# M606B.net
KiCad netlist of a schematic drawn in EAGLE
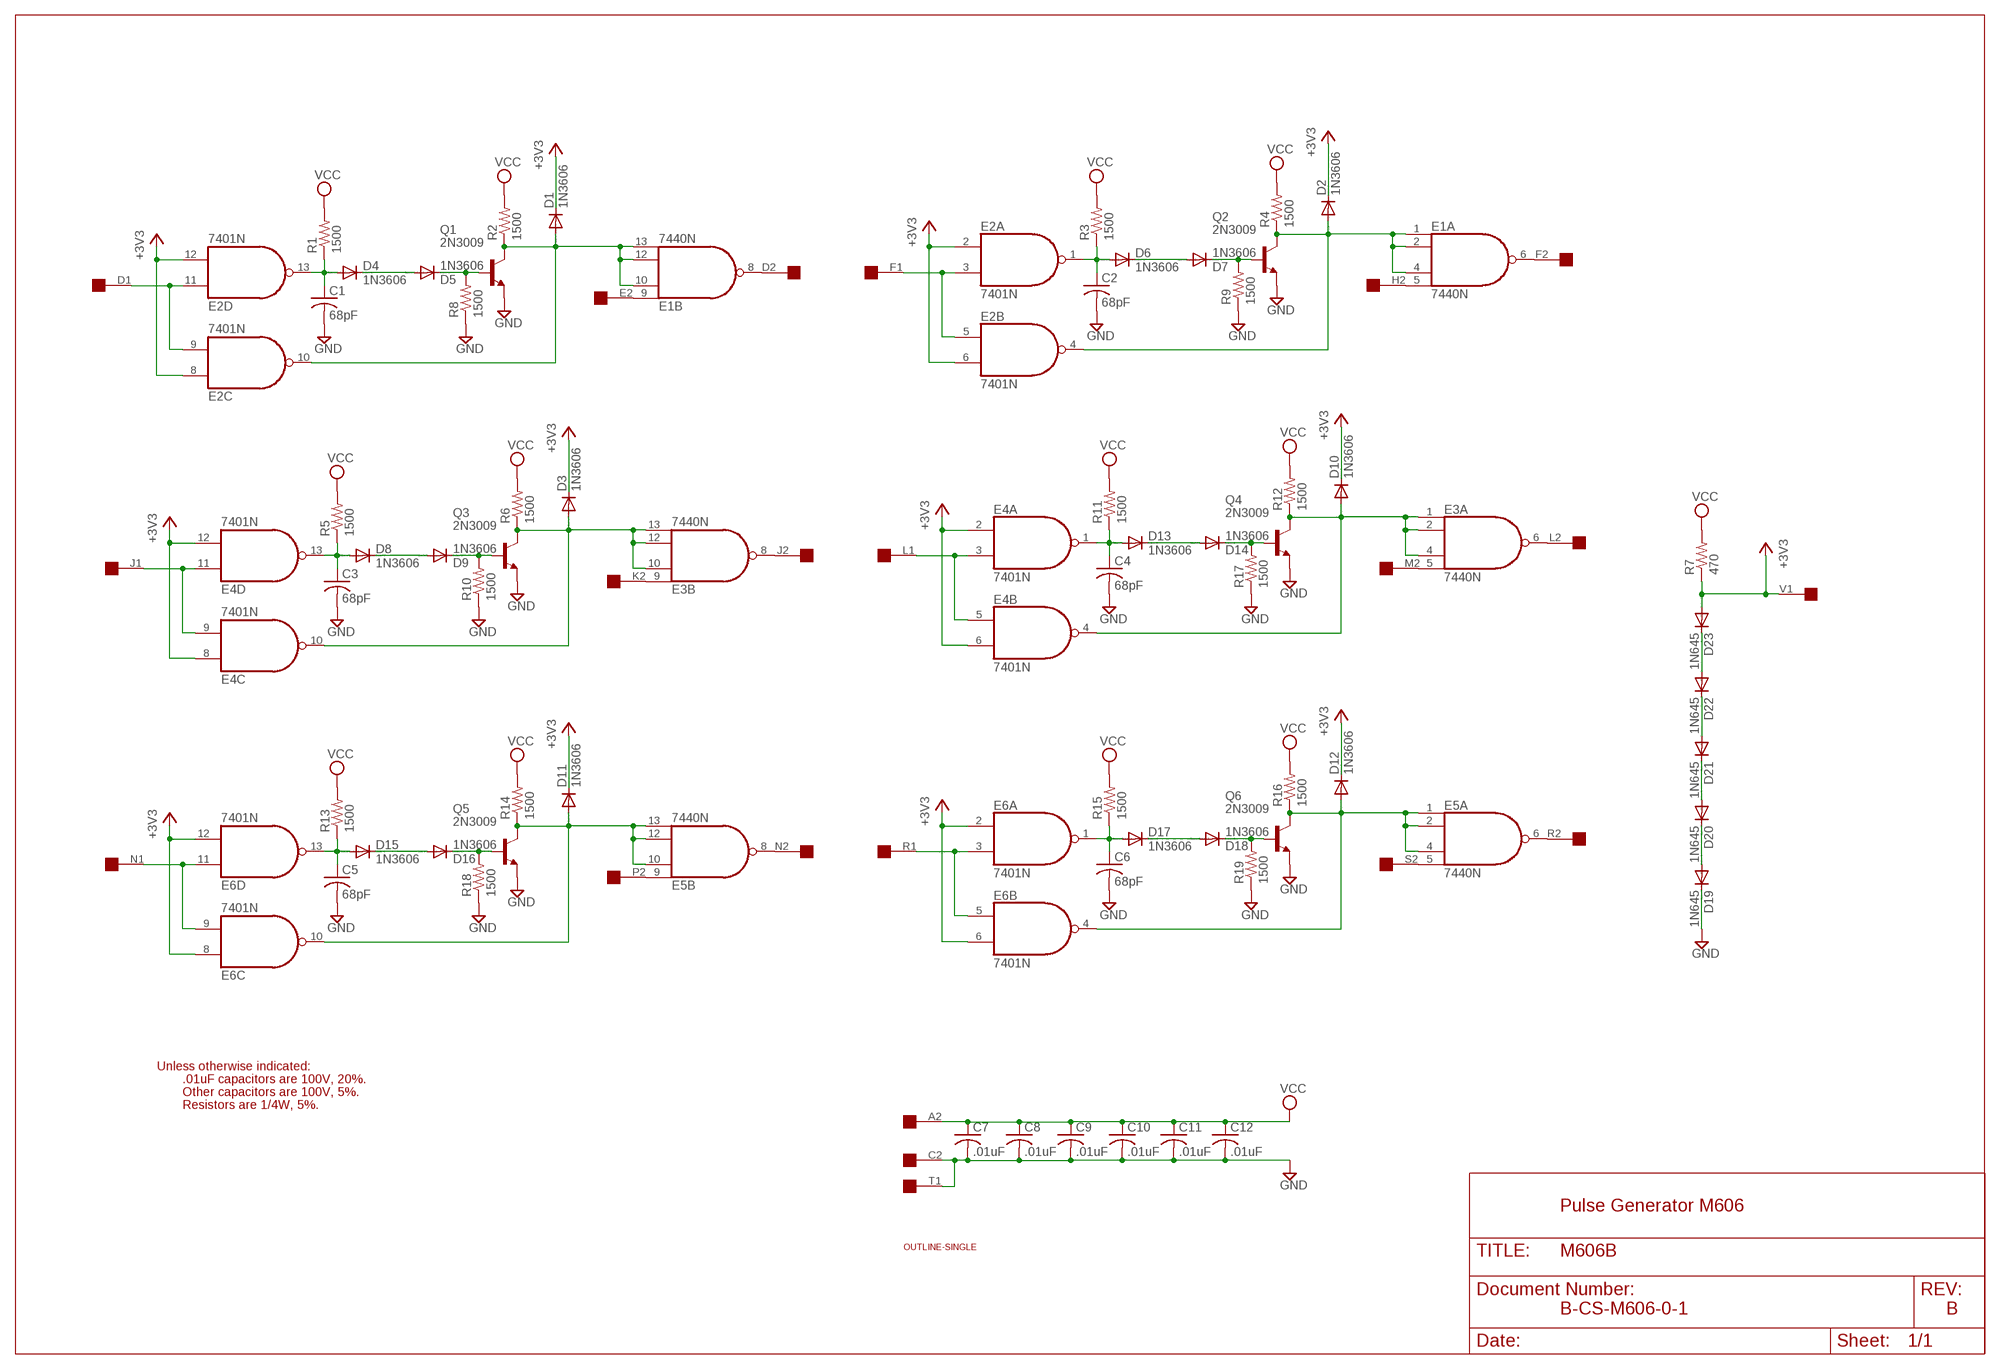
[diagram p0: schematic, sheet 1]

(export (version "E")
  (design (tool "Eeschema 10.0.6"))
  (components
    (comp (ref "C1")
      (value "68pF")
      (footprint "eagle-import:C075-032X103")
      (libsource (lib "eagle-import") (part "C-US075-032X103"))
    )
    (comp (ref "C2")
      (value "68pF")
      (footprint "eagle-import:C075-032X103")
      (libsource (lib "eagle-import") (part "C-US075-032X103"))
    )
    (comp (ref "C3")
      (value "68pF")
      (footprint "eagle-import:C075-032X103")
      (libsource (lib "eagle-import") (part "C-US075-032X103"))
    )
    (comp (ref "C4")
      (value "68pF")
      (footprint "eagle-import:C075-032X103")
      (libsource (lib "eagle-import") (part "C-US075-032X103"))
    )
    (comp (ref "C5")
      (value "68pF")
      (footprint "eagle-import:C075-032X103")
      (libsource (lib "eagle-import") (part "C-US075-032X103"))
    )
    (comp (ref "C6")
      (value "68pF")
      (footprint "eagle-import:C075-032X103")
      (libsource (lib "eagle-import") (part "C-US075-032X103"))
    )
    (comp (ref "C7")
      (value ".01uF")
      (footprint "eagle-import:C050-025X075")
      (libsource (lib "eagle-import") (part "C-US050-025X075"))
    )
    (comp (ref "C8")
      (value ".01uF")
      (footprint "eagle-import:C050-025X075")
      (libsource (lib "eagle-import") (part "C-US050-025X075"))
    )
    (comp (ref "C9")
      (value ".01uF")
      (footprint "eagle-import:C050-025X075")
      (libsource (lib "eagle-import") (part "C-US050-025X075"))
    )
    (comp (ref "C10")
      (value ".01uF")
      (footprint "eagle-import:C050-025X075")
      (libsource (lib "eagle-import") (part "C-US050-025X075"))
    )
    (comp (ref "C11")
      (value ".01uF")
      (footprint "eagle-import:C050-025X075")
      (libsource (lib "eagle-import") (part "C-US050-025X075"))
    )
    (comp (ref "C12")
      (value ".01uF")
      (footprint "eagle-import:C050-025X075")
      (libsource (lib "eagle-import") (part "C-US050-025X075"))
    )
    (comp (ref "D1")
      (value "1N3606")
      (footprint "eagle-import:DO35-10")
      (libsource (lib "eagle-import") (part "1N4148DO35-10"))
    )
    (comp (ref "D2")
      (value "1N3606")
      (footprint "eagle-import:DO35-10")
      (libsource (lib "eagle-import") (part "1N4148DO35-10"))
    )
    (comp (ref "D3")
      (value "1N3606")
      (footprint "eagle-import:DO35-10")
      (libsource (lib "eagle-import") (part "1N4148DO35-10"))
    )
    (comp (ref "D4")
      (value "1N3606")
      (footprint "eagle-import:DO35-10")
      (libsource (lib "eagle-import") (part "1N4148DO35-10"))
    )
    (comp (ref "D5")
      (value "1N3606")
      (footprint "eagle-import:DO35-10")
      (libsource (lib "eagle-import") (part "1N4148DO35-10"))
    )
    (comp (ref "D6")
      (value "1N3606")
      (footprint "eagle-import:DO35-10")
      (libsource (lib "eagle-import") (part "1N4148DO35-10"))
    )
    (comp (ref "D7")
      (value "1N3606")
      (footprint "eagle-import:DO35-10")
      (libsource (lib "eagle-import") (part "1N4148DO35-10"))
    )
    (comp (ref "D8")
      (value "1N3606")
      (footprint "eagle-import:DO35-10")
      (libsource (lib "eagle-import") (part "1N4148DO35-10"))
    )
    (comp (ref "D9")
      (value "1N3606")
      (footprint "eagle-import:DO35-10")
      (libsource (lib "eagle-import") (part "1N4148DO35-10"))
    )
    (comp (ref "D10")
      (value "1N3606")
      (footprint "eagle-import:DO35-10")
      (libsource (lib "eagle-import") (part "1N4148DO35-10"))
    )
    (comp (ref "D11")
      (value "1N3606")
      (footprint "eagle-import:DO35-10")
      (libsource (lib "eagle-import") (part "1N4148DO35-10"))
    )
    (comp (ref "D12")
      (value "1N3606")
      (footprint "eagle-import:DO35-10")
      (libsource (lib "eagle-import") (part "1N4148DO35-10"))
    )
    (comp (ref "D13")
      (value "1N3606")
      (footprint "eagle-import:DO35-10")
      (libsource (lib "eagle-import") (part "1N4148DO35-10"))
    )
    (comp (ref "D14")
      (value "1N3606")
      (footprint "eagle-import:DO35-10")
      (libsource (lib "eagle-import") (part "1N4148DO35-10"))
    )
    (comp (ref "D15")
      (value "1N3606")
      (footprint "eagle-import:DO35-10")
      (libsource (lib "eagle-import") (part "1N4148DO35-10"))
    )
    (comp (ref "D16")
      (value "1N3606")
      (footprint "eagle-import:DO35-10")
      (libsource (lib "eagle-import") (part "1N4148DO35-10"))
    )
    (comp (ref "D17")
      (value "1N3606")
      (footprint "eagle-import:DO35-10")
      (libsource (lib "eagle-import") (part "1N4148DO35-10"))
    )
    (comp (ref "D18")
      (value "1N3606")
      (footprint "eagle-import:DO35-10")
      (libsource (lib "eagle-import") (part "1N4148DO35-10"))
    )
    (comp (ref "D19")
      (value "1N645")
      (footprint "eagle-import:DO35-10")
      (libsource (lib "eagle-import") (part "1N4148DO35-10"))
    )
    (comp (ref "D20")
      (value "1N645")
      (footprint "eagle-import:DO35-10")
      (libsource (lib "eagle-import") (part "1N4148DO35-10"))
    )
    (comp (ref "D21")
      (value "1N645")
      (footprint "eagle-import:DO35-10")
      (libsource (lib "eagle-import") (part "1N4148DO35-10"))
    )
    (comp (ref "D22")
      (value "1N645")
      (footprint "eagle-import:DO35-10")
      (libsource (lib "eagle-import") (part "1N4148DO35-10"))
    )
    (comp (ref "D23")
      (value "1N645")
      (footprint "eagle-import:DO35-10")
      (libsource (lib "eagle-import") (part "1N4148DO35-10"))
    )
    (comp (ref "E1")
      (value "7440N")
      (footprint "eagle-import:DIL14")
      (libsource (lib "eagle-import") (part "7420NS"))
    )
    (comp (ref "E2")
      (value "7401N")
      (footprint "eagle-import:DIL14")
      (libsource (lib "eagle-import") (part "7401NLS"))
    )
    (comp (ref "E3")
      (value "7440N")
      (footprint "eagle-import:DIL14")
      (libsource (lib "eagle-import") (part "7420NS"))
    )
    (comp (ref "E4")
      (value "7401N")
      (footprint "eagle-import:DIL14")
      (libsource (lib "eagle-import") (part "7401NLS"))
    )
    (comp (ref "E5")
      (value "7440N")
      (footprint "eagle-import:DIL14")
      (libsource (lib "eagle-import") (part "7420NS"))
    )
    (comp (ref "E6")
      (value "7401N")
      (footprint "eagle-import:DIL14")
      (libsource (lib "eagle-import") (part "7401NLS"))
    )
    (comp (ref "Q1")
      (value "2N3009")
      (footprint "eagle-import:TO39")
      (libsource (lib "eagle-import") (part "2N3019"))
    )
    (comp (ref "Q2")
      (value "2N3009")
      (footprint "eagle-import:TO39")
      (libsource (lib "eagle-import") (part "2N3019"))
    )
    (comp (ref "Q3")
      (value "2N3009")
      (footprint "eagle-import:TO39")
      (libsource (lib "eagle-import") (part "2N3019"))
    )
    (comp (ref "Q4")
      (value "2N3009")
      (footprint "eagle-import:TO39")
      (libsource (lib "eagle-import") (part "2N3019"))
    )
    (comp (ref "Q5")
      (value "2N3009")
      (footprint "eagle-import:TO39")
      (libsource (lib "eagle-import") (part "2N3019"))
    )
    (comp (ref "Q6")
      (value "2N3009")
      (footprint "eagle-import:TO39")
      (libsource (lib "eagle-import") (part "2N3019"))
    )
    (comp (ref "R1")
      (value "1500")
      (footprint "eagle-import:0207_10")
      (libsource (lib "eagle-import") (part "R-US_0207/10"))
    )
    (comp (ref "R2")
      (value "1500")
      (footprint "eagle-import:0207_10")
      (libsource (lib "eagle-import") (part "R-US_0207/10"))
    )
    (comp (ref "R3")
      (value "1500")
      (footprint "eagle-import:0207_10")
      (libsource (lib "eagle-import") (part "R-US_0207/10"))
    )
    (comp (ref "R4")
      (value "1500")
      (footprint "eagle-import:0207_10")
      (libsource (lib "eagle-import") (part "R-US_0207/10"))
    )
    (comp (ref "R5")
      (value "1500")
      (footprint "eagle-import:0207_10")
      (libsource (lib "eagle-import") (part "R-US_0207/10"))
    )
    (comp (ref "R6")
      (value "1500")
      (footprint "eagle-import:0207_10")
      (libsource (lib "eagle-import") (part "R-US_0207/10"))
    )
    (comp (ref "R7")
      (value "470")
      (footprint "eagle-import:0207_10")
      (libsource (lib "eagle-import") (part "R-US_0207/10"))
    )
    (comp (ref "R8")
      (value "1500")
      (footprint "eagle-import:0207_10")
      (libsource (lib "eagle-import") (part "R-US_0207/10"))
    )
    (comp (ref "R9")
      (value "1500")
      (footprint "eagle-import:0207_10")
      (libsource (lib "eagle-import") (part "R-US_0207/10"))
    )
    (comp (ref "R10")
      (value "1500")
      (footprint "eagle-import:0207_10")
      (libsource (lib "eagle-import") (part "R-US_0207/10"))
    )
    (comp (ref "R11")
      (value "1500")
      (footprint "eagle-import:0207_10")
      (libsource (lib "eagle-import") (part "R-US_0207/10"))
    )
    (comp (ref "R12")
      (value "1500")
      (footprint "eagle-import:0207_10")
      (libsource (lib "eagle-import") (part "R-US_0207/10"))
    )
    (comp (ref "R13")
      (value "1500")
      (footprint "eagle-import:0207_10")
      (libsource (lib "eagle-import") (part "R-US_0207/10"))
    )
    (comp (ref "R14")
      (value "1500")
      (footprint "eagle-import:0207_10")
      (libsource (lib "eagle-import") (part "R-US_0207/10"))
    )
    (comp (ref "R15")
      (value "1500")
      (footprint "eagle-import:0207_10")
      (libsource (lib "eagle-import") (part "R-US_0207/10"))
    )
    (comp (ref "R16")
      (value "1500")
      (footprint "eagle-import:0207_10")
      (libsource (lib "eagle-import") (part "R-US_0207/10"))
    )
    (comp (ref "R17")
      (value "1500")
      (footprint "eagle-import:0207_10")
      (libsource (lib "eagle-import") (part "R-US_0207/10"))
    )
    (comp (ref "R18")
      (value "1500")
      (footprint "eagle-import:0207_10")
      (libsource (lib "eagle-import") (part "R-US_0207/10"))
    )
    (comp (ref "R19")
      (value "1500")
      (footprint "eagle-import:0207_10")
      (libsource (lib "eagle-import") (part "R-US_0207/10"))
    )
    (comp (ref "U$2")
      (value "SINGLE")
      (footprint "eagle-import:EDGE-CON2")
      (libsource (lib "eagle-import") (part "SINGLE"))
    )
    (comp (ref "U$4")
      (value "OUTLINE-SINGLE")
      (footprint "eagle-import:SINGLE")
      (libsource (lib "eagle-import") (part "OUTLINE-SINGLE"))
    )
  )
  (nets
    (net (code "1") (name "+3V3") (class "Default")
      (node (ref "D1") (pin "C") (pinfunction "C_C") (pintype "passive"))
      (node (ref "D10") (pin "C") (pinfunction "C_C") (pintype "passive"))
      (node (ref "D11") (pin "C") (pinfunction "C_C") (pintype "passive"))
      (node (ref "D12") (pin "C") (pinfunction "C_C") (pintype "passive"))
      (node (ref "D2") (pin "C") (pinfunction "C_C") (pintype "passive"))
      (node (ref "D23") (pin "A") (pinfunction "A_A") (pintype "passive"))
      (node (ref "D3") (pin "C") (pinfunction "C_C") (pintype "passive"))
      (node (ref "E2") (pin "12") (pinfunction "I1_12") (pintype "input"))
      (node (ref "E2") (pin "2") (pinfunction "I0_2") (pintype "input"))
      (node (ref "E2") (pin "6") (pinfunction "I1_6") (pintype "input"))
      (node (ref "E2") (pin "8") (pinfunction "I0_8") (pintype "input"))
      (node (ref "E4") (pin "12") (pinfunction "I1_12") (pintype "input"))
      (node (ref "E4") (pin "2") (pinfunction "I0_2") (pintype "input"))
      (node (ref "E4") (pin "6") (pinfunction "I1_6") (pintype "input"))
      (node (ref "E4") (pin "8") (pinfunction "I0_8") (pintype "input"))
      (node (ref "E6") (pin "12") (pinfunction "I1_12") (pintype "input"))
      (node (ref "E6") (pin "2") (pinfunction "I0_2") (pintype "input"))
      (node (ref "E6") (pin "6") (pinfunction "I1_6") (pintype "input"))
      (node (ref "E6") (pin "8") (pinfunction "I0_8") (pintype "input"))
      (node (ref "R7") (pin "1") (pinfunction "1_1") (pintype "passive"))
      (node (ref "U$2") (pin "V1") (pinfunction "1_V1") (pintype "bidirectional"))
    )
    (net (code "2") (name "GND") (class "Default")
      (node (ref "C1") (pin "2") (pinfunction "2_2") (pintype "passive"))
      (node (ref "C10") (pin "2") (pinfunction "2_2") (pintype "passive"))
      (node (ref "C11") (pin "2") (pinfunction "2_2") (pintype "passive"))
      (node (ref "C12") (pin "2") (pinfunction "2_2") (pintype "passive"))
      (node (ref "C2") (pin "2") (pinfunction "2_2") (pintype "passive"))
      (node (ref "C3") (pin "2") (pinfunction "2_2") (pintype "passive"))
      (node (ref "C4") (pin "2") (pinfunction "2_2") (pintype "passive"))
      (node (ref "C5") (pin "2") (pinfunction "2_2") (pintype "passive"))
      (node (ref "C6") (pin "2") (pinfunction "2_2") (pintype "passive"))
      (node (ref "C7") (pin "2") (pinfunction "2_2") (pintype "passive"))
      (node (ref "C8") (pin "2") (pinfunction "2_2") (pintype "passive"))
      (node (ref "C9") (pin "2") (pinfunction "2_2") (pintype "passive"))
      (node (ref "D19") (pin "C") (pinfunction "C_C") (pintype "passive"))
      (node (ref "Q1") (pin "1") (pinfunction "E_1") (pintype "passive"))
      (node (ref "Q2") (pin "1") (pinfunction "E_1") (pintype "passive"))
      (node (ref "Q3") (pin "1") (pinfunction "E_1") (pintype "passive"))
      (node (ref "Q4") (pin "1") (pinfunction "E_1") (pintype "passive"))
      (node (ref "Q5") (pin "1") (pinfunction "E_1") (pintype "passive"))
      (node (ref "Q6") (pin "1") (pinfunction "E_1") (pintype "passive"))
      (node (ref "R10") (pin "1") (pinfunction "1_1") (pintype "passive"))
      (node (ref "R17") (pin "1") (pinfunction "1_1") (pintype "passive"))
      (node (ref "R18") (pin "1") (pinfunction "1_1") (pintype "passive"))
      (node (ref "R19") (pin "1") (pinfunction "1_1") (pintype "passive"))
      (node (ref "R8") (pin "1") (pinfunction "1_1") (pintype "passive"))
      (node (ref "R9") (pin "1") (pinfunction "1_1") (pintype "passive"))
      (node (ref "U$2") (pin "C2") (pinfunction "1_C2") (pintype "bidirectional"))
      (node (ref "U$2") (pin "T1") (pinfunction "1_T1") (pintype "bidirectional"))
    )
    (net (code "3") (name "Net-(D4-PadC)") (class "Default")
      (node (ref "D4") (pin "C") (pinfunction "C_C") (pintype "passive"))
      (node (ref "D5") (pin "A") (pinfunction "A_A") (pintype "passive"))
    )
    (net (code "4") (name "Net-(D6-PadC)") (class "Default")
      (node (ref "D6") (pin "C") (pinfunction "C_C") (pintype "passive"))
      (node (ref "D7") (pin "A") (pinfunction "A_A") (pintype "passive"))
    )
    (net (code "5") (name "Net-(D8-PadC)") (class "Default")
      (node (ref "D8") (pin "C") (pinfunction "C_C") (pintype "passive"))
      (node (ref "D9") (pin "A") (pinfunction "A_A") (pintype "passive"))
    )
    (net (code "6") (name "Net-(D13-PadC)") (class "Default")
      (node (ref "D13") (pin "C") (pinfunction "C_C") (pintype "passive"))
      (node (ref "D14") (pin "A") (pinfunction "A_A") (pintype "passive"))
    )
    (net (code "7") (name "Net-(D15-PadC)") (class "Default")
      (node (ref "D15") (pin "C") (pinfunction "C_C") (pintype "passive"))
      (node (ref "D16") (pin "A") (pinfunction "A_A") (pintype "passive"))
    )
    (net (code "8") (name "Net-(D17-PadC)") (class "Default")
      (node (ref "D17") (pin "C") (pinfunction "C_C") (pintype "passive"))
      (node (ref "D18") (pin "A") (pinfunction "A_A") (pintype "passive"))
    )
    (net (code "9") (name "Net-(D19-PadA)") (class "Default")
      (node (ref "D19") (pin "A") (pinfunction "A_A") (pintype "passive"))
      (node (ref "D20") (pin "C") (pinfunction "C_C") (pintype "passive"))
    )
    (net (code "10") (name "Net-(D20-PadA)") (class "Default")
      (node (ref "D20") (pin "A") (pinfunction "A_A") (pintype "passive"))
      (node (ref "D21") (pin "C") (pinfunction "C_C") (pintype "passive"))
    )
    (net (code "11") (name "Net-(D21-PadA)") (class "Default")
      (node (ref "D21") (pin "A") (pinfunction "A_A") (pintype "passive"))
      (node (ref "D22") (pin "C") (pinfunction "C_C") (pintype "passive"))
    )
    (net (code "12") (name "Net-(D22-PadA)") (class "Default")
      (node (ref "D22") (pin "A") (pinfunction "A_A") (pintype "passive"))
      (node (ref "D23") (pin "C") (pinfunction "C_C") (pintype "passive"))
    )
    (net (code "13") (name "Net-(E1A-I0)") (class "Default")
      (node (ref "D2") (pin "A") (pinfunction "A_A") (pintype "passive"))
      (node (ref "E1") (pin "1") (pinfunction "I0_1") (pintype "input"))
      (node (ref "E1") (pin "2") (pinfunction "I1_2") (pintype "input"))
      (node (ref "E1") (pin "4") (pinfunction "I2_4") (pintype "input"))
      (node (ref "E2") (pin "4") (pinfunction "O_4") (pintype "open_collector"))
      (node (ref "Q2") (pin "3") (pinfunction "C_3") (pintype "passive"))
      (node (ref "R4") (pin "1") (pinfunction "1_1") (pintype "passive"))
    )
    (net (code "14") (name "Net-(E1A-I3)") (class "Default")
      (node (ref "E1") (pin "5") (pinfunction "I3_5") (pintype "input"))
      (node (ref "U$2") (pin "H2") (pinfunction "1_H2") (pintype "bidirectional"))
    )
    (net (code "15") (name "Net-(E1A-O)") (class "Default")
      (node (ref "E1") (pin "6") (pinfunction "O_6") (pintype "output"))
      (node (ref "U$2") (pin "F2") (pinfunction "1_F2") (pintype "bidirectional"))
    )
    (net (code "16") (name "Net-(E1B-I0)") (class "Default")
      (node (ref "E1") (pin "9") (pinfunction "I0_9") (pintype "input"))
      (node (ref "U$2") (pin "E2") (pinfunction "1_E2") (pintype "bidirectional"))
    )
    (net (code "17") (name "Net-(E1B-I1)") (class "Default")
      (node (ref "D1") (pin "A") (pinfunction "A_A") (pintype "passive"))
      (node (ref "E1") (pin "10") (pinfunction "I1_10") (pintype "input"))
      (node (ref "E1") (pin "12") (pinfunction "I2_12") (pintype "input"))
      (node (ref "E1") (pin "13") (pinfunction "I3_13") (pintype "input"))
      (node (ref "E2") (pin "10") (pinfunction "O_10") (pintype "open_collector"))
      (node (ref "Q1") (pin "3") (pinfunction "C_3") (pintype "passive"))
      (node (ref "R2") (pin "1") (pinfunction "1_1") (pintype "passive"))
    )
    (net (code "18") (name "Net-(E1B-O)") (class "Default")
      (node (ref "E1") (pin "8") (pinfunction "O_8") (pintype "output"))
      (node (ref "U$2") (pin "D2") (pinfunction "1_D2") (pintype "bidirectional"))
    )
    (net (code "19") (name "Net-(E2A-I1)") (class "Default")
      (node (ref "E2") (pin "3") (pinfunction "I1_3") (pintype "input"))
      (node (ref "E2") (pin "5") (pinfunction "I0_5") (pintype "input"))
      (node (ref "U$2") (pin "F1") (pinfunction "1_F1") (pintype "bidirectional"))
    )
    (net (code "20") (name "Net-(E2A-O)") (class "Default")
      (node (ref "C2") (pin "1") (pinfunction "1_1") (pintype "passive"))
      (node (ref "D6") (pin "A") (pinfunction "A_A") (pintype "passive"))
      (node (ref "E2") (pin "1") (pinfunction "O_1") (pintype "open_collector"))
      (node (ref "R3") (pin "1") (pinfunction "1_1") (pintype "passive"))
    )
    (net (code "21") (name "Net-(E2C-I1)") (class "Default")
      (node (ref "E2") (pin "11") (pinfunction "I0_11") (pintype "input"))
      (node (ref "E2") (pin "9") (pinfunction "I1_9") (pintype "input"))
      (node (ref "U$2") (pin "D1") (pinfunction "1_D1") (pintype "bidirectional"))
    )
    (net (code "22") (name "Net-(E2D-O)") (class "Default")
      (node (ref "C1") (pin "1") (pinfunction "1_1") (pintype "passive"))
      (node (ref "D4") (pin "A") (pinfunction "A_A") (pintype "passive"))
      (node (ref "E2") (pin "13") (pinfunction "O_13") (pintype "open_collector"))
      (node (ref "R1") (pin "1") (pinfunction "1_1") (pintype "passive"))
    )
    (net (code "23") (name "Net-(E3A-I0)") (class "Default")
      (node (ref "D10") (pin "A") (pinfunction "A_A") (pintype "passive"))
      (node (ref "E3") (pin "1") (pinfunction "I0_1") (pintype "input"))
      (node (ref "E3") (pin "2") (pinfunction "I1_2") (pintype "input"))
      (node (ref "E3") (pin "4") (pinfunction "I2_4") (pintype "input"))
      (node (ref "E4") (pin "4") (pinfunction "O_4") (pintype "open_collector"))
      (node (ref "Q4") (pin "3") (pinfunction "C_3") (pintype "passive"))
      (node (ref "R12") (pin "1") (pinfunction "1_1") (pintype "passive"))
    )
    (net (code "24") (name "Net-(E3A-I3)") (class "Default")
      (node (ref "E3") (pin "5") (pinfunction "I3_5") (pintype "input"))
      (node (ref "U$2") (pin "M2") (pinfunction "1_M2") (pintype "bidirectional"))
    )
    (net (code "25") (name "Net-(E3A-O)") (class "Default")
      (node (ref "E3") (pin "6") (pinfunction "O_6") (pintype "output"))
      (node (ref "U$2") (pin "L2") (pinfunction "1_L2") (pintype "bidirectional"))
    )
    (net (code "26") (name "Net-(E3B-I0)") (class "Default")
      (node (ref "E3") (pin "9") (pinfunction "I0_9") (pintype "input"))
      (node (ref "U$2") (pin "K2") (pinfunction "1_K2") (pintype "bidirectional"))
    )
    (net (code "27") (name "Net-(E3B-I1)") (class "Default")
      (node (ref "D3") (pin "A") (pinfunction "A_A") (pintype "passive"))
      (node (ref "E3") (pin "10") (pinfunction "I1_10") (pintype "input"))
      (node (ref "E3") (pin "12") (pinfunction "I2_12") (pintype "input"))
      (node (ref "E3") (pin "13") (pinfunction "I3_13") (pintype "input"))
      (node (ref "E4") (pin "10") (pinfunction "O_10") (pintype "open_collector"))
      (node (ref "Q3") (pin "3") (pinfunction "C_3") (pintype "passive"))
      (node (ref "R6") (pin "1") (pinfunction "1_1") (pintype "passive"))
    )
    (net (code "28") (name "Net-(E3B-O)") (class "Default")
      (node (ref "E3") (pin "8") (pinfunction "O_8") (pintype "output"))
      (node (ref "U$2") (pin "J2") (pinfunction "1_J2") (pintype "bidirectional"))
    )
    (net (code "29") (name "Net-(E4A-I1)") (class "Default")
      (node (ref "E4") (pin "3") (pinfunction "I1_3") (pintype "input"))
      (node (ref "E4") (pin "5") (pinfunction "I0_5") (pintype "input"))
      (node (ref "U$2") (pin "L1") (pinfunction "1_L1") (pintype "bidirectional"))
    )
    (net (code "30") (name "Net-(E4A-O)") (class "Default")
      (node (ref "C4") (pin "1") (pinfunction "1_1") (pintype "passive"))
      (node (ref "D13") (pin "A") (pinfunction "A_A") (pintype "passive"))
      (node (ref "E4") (pin "1") (pinfunction "O_1") (pintype "open_collector"))
      (node (ref "R11") (pin "1") (pinfunction "1_1") (pintype "passive"))
    )
    (net (code "31") (name "Net-(E4C-I1)") (class "Default")
      (node (ref "E4") (pin "11") (pinfunction "I0_11") (pintype "input"))
      (node (ref "E4") (pin "9") (pinfunction "I1_9") (pintype "input"))
      (node (ref "U$2") (pin "J1") (pinfunction "1_J1") (pintype "bidirectional"))
    )
    (net (code "32") (name "Net-(E4D-O)") (class "Default")
      (node (ref "C3") (pin "1") (pinfunction "1_1") (pintype "passive"))
      (node (ref "D8") (pin "A") (pinfunction "A_A") (pintype "passive"))
      (node (ref "E4") (pin "13") (pinfunction "O_13") (pintype "open_collector"))
      (node (ref "R5") (pin "1") (pinfunction "1_1") (pintype "passive"))
    )
    (net (code "33") (name "Net-(E5A-I0)") (class "Default")
      (node (ref "D12") (pin "A") (pinfunction "A_A") (pintype "passive"))
      (node (ref "E5") (pin "1") (pinfunction "I0_1") (pintype "input"))
      (node (ref "E5") (pin "2") (pinfunction "I1_2") (pintype "input"))
      (node (ref "E5") (pin "4") (pinfunction "I2_4") (pintype "input"))
      (node (ref "E6") (pin "4") (pinfunction "O_4") (pintype "open_collector"))
      (node (ref "Q6") (pin "3") (pinfunction "C_3") (pintype "passive"))
      (node (ref "R16") (pin "1") (pinfunction "1_1") (pintype "passive"))
    )
    (net (code "34") (name "Net-(E5A-I3)") (class "Default")
      (node (ref "E5") (pin "5") (pinfunction "I3_5") (pintype "input"))
      (node (ref "U$2") (pin "S2") (pinfunction "1_S2") (pintype "bidirectional"))
    )
    (net (code "35") (name "Net-(E5A-O)") (class "Default")
      (node (ref "E5") (pin "6") (pinfunction "O_6") (pintype "output"))
      (node (ref "U$2") (pin "R2") (pinfunction "1_R2") (pintype "bidirectional"))
    )
    (net (code "36") (name "Net-(E5B-I0)") (class "Default")
      (node (ref "E5") (pin "9") (pinfunction "I0_9") (pintype "input"))
      (node (ref "U$2") (pin "P2") (pinfunction "1_P2") (pintype "bidirectional"))
    )
    (net (code "37") (name "Net-(E5B-I1)") (class "Default")
      (node (ref "D11") (pin "A") (pinfunction "A_A") (pintype "passive"))
      (node (ref "E5") (pin "10") (pinfunction "I1_10") (pintype "input"))
      (node (ref "E5") (pin "12") (pinfunction "I2_12") (pintype "input"))
      (node (ref "E5") (pin "13") (pinfunction "I3_13") (pintype "input"))
      (node (ref "E6") (pin "10") (pinfunction "O_10") (pintype "open_collector"))
      (node (ref "Q5") (pin "3") (pinfunction "C_3") (pintype "passive"))
      (node (ref "R14") (pin "1") (pinfunction "1_1") (pintype "passive"))
    )
    (net (code "38") (name "Net-(E5B-O)") (class "Default")
      (node (ref "E5") (pin "8") (pinfunction "O_8") (pintype "output"))
      (node (ref "U$2") (pin "N2") (pinfunction "1_N2") (pintype "bidirectional"))
    )
    (net (code "39") (name "Net-(E6A-I1)") (class "Default")
      (node (ref "E6") (pin "3") (pinfunction "I1_3") (pintype "input"))
      (node (ref "E6") (pin "5") (pinfunction "I0_5") (pintype "input"))
      (node (ref "U$2") (pin "R1") (pinfunction "1_R1") (pintype "bidirectional"))
    )
    (net (code "40") (name "Net-(E6A-O)") (class "Default")
      (node (ref "C6") (pin "1") (pinfunction "1_1") (pintype "passive"))
      (node (ref "D17") (pin "A") (pinfunction "A_A") (pintype "passive"))
      (node (ref "E6") (pin "1") (pinfunction "O_1") (pintype "open_collector"))
      (node (ref "R15") (pin "1") (pinfunction "1_1") (pintype "passive"))
    )
    (net (code "41") (name "Net-(E6C-I1)") (class "Default")
      (node (ref "E6") (pin "11") (pinfunction "I0_11") (pintype "input"))
      (node (ref "E6") (pin "9") (pinfunction "I1_9") (pintype "input"))
      (node (ref "U$2") (pin "N1") (pinfunction "1_N1") (pintype "bidirectional"))
    )
    (net (code "42") (name "Net-(E6D-O)") (class "Default")
      (node (ref "C5") (pin "1") (pinfunction "1_1") (pintype "passive"))
      (node (ref "D15") (pin "A") (pinfunction "A_A") (pintype "passive"))
      (node (ref "E6") (pin "13") (pinfunction "O_13") (pintype "open_collector"))
      (node (ref "R13") (pin "1") (pinfunction "1_1") (pintype "passive"))
    )
    (net (code "43") (name "Net-(Q1-B)") (class "Default")
      (node (ref "D5") (pin "C") (pinfunction "C_C") (pintype "passive"))
      (node (ref "Q1") (pin "2") (pinfunction "B_2") (pintype "passive"))
      (node (ref "R8") (pin "2") (pinfunction "2_2") (pintype "passive"))
    )
    (net (code "44") (name "Net-(Q2-B)") (class "Default")
      (node (ref "D7") (pin "C") (pinfunction "C_C") (pintype "passive"))
      (node (ref "Q2") (pin "2") (pinfunction "B_2") (pintype "passive"))
      (node (ref "R9") (pin "2") (pinfunction "2_2") (pintype "passive"))
    )
    (net (code "45") (name "Net-(Q3-B)") (class "Default")
      (node (ref "D9") (pin "C") (pinfunction "C_C") (pintype "passive"))
      (node (ref "Q3") (pin "2") (pinfunction "B_2") (pintype "passive"))
      (node (ref "R10") (pin "2") (pinfunction "2_2") (pintype "passive"))
    )
    (net (code "46") (name "Net-(Q4-B)") (class "Default")
      (node (ref "D14") (pin "C") (pinfunction "C_C") (pintype "passive"))
      (node (ref "Q4") (pin "2") (pinfunction "B_2") (pintype "passive"))
      (node (ref "R17") (pin "2") (pinfunction "2_2") (pintype "passive"))
    )
    (net (code "47") (name "Net-(Q5-B)") (class "Default")
      (node (ref "D16") (pin "C") (pinfunction "C_C") (pintype "passive"))
      (node (ref "Q5") (pin "2") (pinfunction "B_2") (pintype "passive"))
      (node (ref "R18") (pin "2") (pinfunction "2_2") (pintype "passive"))
    )
    (net (code "48") (name "Net-(Q6-B)") (class "Default")
      (node (ref "D18") (pin "C") (pinfunction "C_C") (pintype "passive"))
      (node (ref "Q6") (pin "2") (pinfunction "B_2") (pintype "passive"))
      (node (ref "R19") (pin "2") (pinfunction "2_2") (pintype "passive"))
    )
    (net (code "49") (name "VCC") (class "Default")
      (node (ref "C10") (pin "1") (pinfunction "1_1") (pintype "passive"))
      (node (ref "C11") (pin "1") (pinfunction "1_1") (pintype "passive"))
      (node (ref "C12") (pin "1") (pinfunction "1_1") (pintype "passive"))
      (node (ref "C7") (pin "1") (pinfunction "1_1") (pintype "passive"))
      (node (ref "C8") (pin "1") (pinfunction "1_1") (pintype "passive"))
      (node (ref "C9") (pin "1") (pinfunction "1_1") (pintype "passive"))
      (node (ref "R1") (pin "2") (pinfunction "2_2") (pintype "passive"))
      (node (ref "R11") (pin "2") (pinfunction "2_2") (pintype "passive"))
      (node (ref "R12") (pin "2") (pinfunction "2_2") (pintype "passive"))
      (node (ref "R13") (pin "2") (pinfunction "2_2") (pintype "passive"))
      (node (ref "R14") (pin "2") (pinfunction "2_2") (pintype "passive"))
      (node (ref "R15") (pin "2") (pinfunction "2_2") (pintype "passive"))
      (node (ref "R16") (pin "2") (pinfunction "2_2") (pintype "passive"))
      (node (ref "R2") (pin "2") (pinfunction "2_2") (pintype "passive"))
      (node (ref "R3") (pin "2") (pinfunction "2_2") (pintype "passive"))
      (node (ref "R4") (pin "2") (pinfunction "2_2") (pintype "passive"))
      (node (ref "R5") (pin "2") (pinfunction "2_2") (pintype "passive"))
      (node (ref "R6") (pin "2") (pinfunction "2_2") (pintype "passive"))
      (node (ref "R7") (pin "2") (pinfunction "2_2") (pintype "passive"))
      (node (ref "U$2") (pin "A2") (pinfunction "1_A2") (pintype "bidirectional"))
    )
  )
)
